# Sheet1.net
KiCad netlist of a schematic drawn in Altium Designer
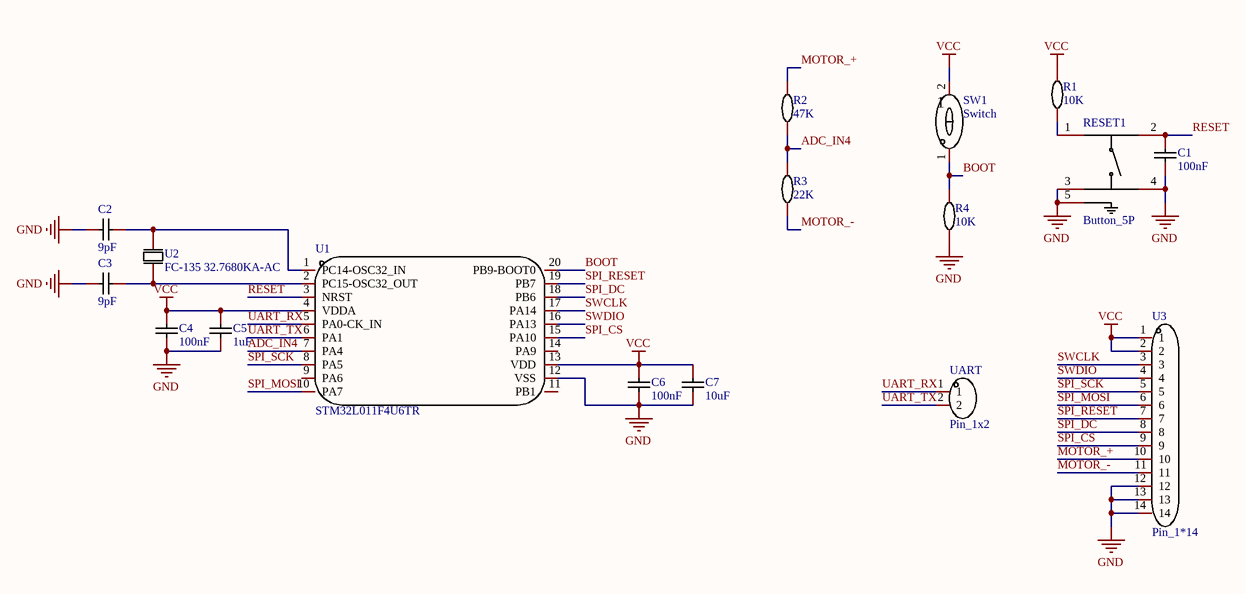
[diagram p0: Sheet1.SchDoc]

(export (version "E")
  (design (tool "Eeschema 10.0.6"))
  (components
    (comp (ref "C1") (value "100nF") (footprint "C0402") (libsource (lib "MySchlib") (part "C")))
    (comp (ref "C2") (value "9pF") (footprint "C0402") (libsource (lib "MySchlib") (part "C")))
    (comp (ref "C3") (value "9pF") (footprint "C0402") (libsource (lib "MySchlib") (part "C")))
    (comp (ref "C4") (value "100nF") (footprint "C0402") (libsource (lib "MySchlib") (part "C")))
    (comp (ref "C5") (value "1uF") (footprint "C0402") (libsource (lib "MySchlib") (part "C")))
    (comp (ref "C6") (value "100nF") (footprint "C0402") (libsource (lib "MySchlib") (part "C")))
    (comp (ref "C7") (value "10uF") (footprint "C0402") (libsource (lib "MySchlib") (part "C")))
    (comp (ref "R1") (value "10K") (footprint "R0603") (libsource (lib "MySchlib") (part "R")))
    (comp (ref "R2") (value "47K") (footprint "R0603") (libsource (lib "MySchlib") (part "R")))
    (comp (ref "R3") (value "22K") (footprint "R0603") (libsource (lib "MySchlib") (part "R")))
    (comp (ref "R4") (value "10K") (footprint "R0603") (libsource (lib "MySchlib") (part "R")))
    (comp (ref "RESET1")
      (value "Button_5P")
      (footprint "Button_3.3x3.3mm")
      (libsource (lib "MySchlib") (part "Button_5P"))
    )
    (comp (ref "SW1") (value "Switch") (footprint "Switch") (libsource (lib "MySchlib") (part "Switch")))
    (comp (ref "U1")
      (value "STM32L011F4U6TR")
      (footprint "STM32L011F4")
      (libsource (lib "MySchlib") (part "STM32L011F4"))
    )
    (comp (ref "U2")
      (value "FC-135 32.7680KA-AC")
      (footprint "CRYSTAL-SMD_L3.2-W1.5")
      (libsource (lib "MySchlib") (part "FC-135 32.7680KA-AC"))
    )
    (comp (ref "U3") (value "Pin_1*14") (footprint "Pin_1*14") (libsource (lib "MySchlib") (part "Pin_1*14")))
    (comp (ref "UART")
      (value "Pin_1x2")
      (footprint "Pin1x2_2.54mm")
      (libsource (lib "MySchlib") (part "Pin_1x2"))
    )
  )
  (nets
    (net (code "1") (name "/ADC_IN4") (class "Default")
      (node (ref "R2") (pin "1") (pinfunction "1_1") (pintype "passive"))
      (node (ref "R3") (pin "2") (pinfunction "2_2") (pintype "passive"))
      (node (ref "U1") (pin "7") (pinfunction "PA4_7") (pintype "passive"))
    )
    (net (code "2") (name "/BOOT") (class "Default")
      (node (ref "R4") (pin "2") (pinfunction "2_2") (pintype "passive"))
      (node (ref "SW1") (pin "1") (pinfunction "PIN1_1") (pintype "passive"))
      (node (ref "U1") (pin "20") (pinfunction "PB9-BOOT0_20") (pintype "passive"))
    )
    (net (code "3") (name "/MOTOR_+") (class "Default")
      (node (ref "R2") (pin "2") (pinfunction "2_2") (pintype "passive"))
      (node (ref "U3") (pin "10") (pinfunction "10_10") (pintype "passive"))
    )
    (net (code "4") (name "/MOTOR_-") (class "Default")
      (node (ref "R3") (pin "1") (pinfunction "1_1") (pintype "passive"))
      (node (ref "U3") (pin "11") (pinfunction "11_11") (pintype "passive"))
    )
    (net (code "5") (name "/RESET") (class "Default")
      (node (ref "C1") (pin "2") (pinfunction "2_2") (pintype "passive"))
      (node (ref "RESET1") (pin "2") (pinfunction "B_2") (pintype "passive"))
      (node (ref "U1") (pin "3") (pinfunction "NRST_3") (pintype "passive"))
    )
    (net (code "6") (name "/SPI_CS") (class "Default")
      (node (ref "U1") (pin "15") (pinfunction "PA10_15") (pintype "passive"))
      (node (ref "U3") (pin "9") (pinfunction "9_9") (pintype "passive"))
    )
    (net (code "7") (name "/SPI_DC") (class "Default")
      (node (ref "U1") (pin "18") (pinfunction "PB6_18") (pintype "passive"))
      (node (ref "U3") (pin "8") (pinfunction "8_8") (pintype "passive"))
    )
    (net (code "8") (name "/SPI_MOSI") (class "Default")
      (node (ref "U1") (pin "10") (pinfunction "PA7_10") (pintype "passive"))
      (node (ref "U3") (pin "6") (pinfunction "6_6") (pintype "passive"))
    )
    (net (code "9") (name "/SPI_RESET") (class "Default")
      (node (ref "U1") (pin "19") (pinfunction "PB7_19") (pintype "passive"))
      (node (ref "U3") (pin "7") (pinfunction "7_7") (pintype "passive"))
    )
    (net (code "10") (name "/SPI_SCK") (class "Default")
      (node (ref "U1") (pin "8") (pinfunction "PA5_8") (pintype "passive"))
      (node (ref "U3") (pin "5") (pinfunction "5_5") (pintype "passive"))
    )
    (net (code "11") (name "/SWCLK") (class "Default")
      (node (ref "U1") (pin "17") (pinfunction "PA14_17") (pintype "passive"))
      (node (ref "U3") (pin "3") (pinfunction "3_3") (pintype "passive"))
    )
    (net (code "12") (name "/SWDIO") (class "Default")
      (node (ref "U1") (pin "16") (pinfunction "PA13_16") (pintype "passive"))
      (node (ref "U3") (pin "4") (pinfunction "4_4") (pintype "passive"))
    )
    (net (code "13") (name "/UART_RX") (class "Default")
      (node (ref "U1") (pin "5") (pinfunction "PA0-CK_IN_5") (pintype "passive"))
      (node (ref "UART") (pin "1") (pinfunction "1_1") (pintype "passive"))
    )
    (net (code "14") (name "/UART_TX") (class "Default")
      (node (ref "U1") (pin "6") (pinfunction "PA1_6") (pintype "passive"))
      (node (ref "UART") (pin "2") (pinfunction "2_2") (pintype "passive"))
    )
    (net (code "15") (name "GND") (class "Default")
      (node (ref "C1") (pin "1") (pinfunction "1_1") (pintype "passive"))
      (node (ref "C2") (pin "1") (pinfunction "1_1") (pintype "passive"))
      (node (ref "C3") (pin "1") (pinfunction "1_1") (pintype "passive"))
      (node (ref "C4") (pin "1") (pinfunction "1_1") (pintype "passive"))
      (node (ref "C5") (pin "1") (pinfunction "1_1") (pintype "passive"))
      (node (ref "C6") (pin "1") (pinfunction "1_1") (pintype "passive"))
      (node (ref "C7") (pin "1") (pinfunction "1_1") (pintype "passive"))
      (node (ref "R4") (pin "1") (pinfunction "1_1") (pintype "passive"))
      (node (ref "RESET1") (pin "3") (pinfunction "C_3") (pintype "passive"))
      (node (ref "RESET1") (pin "4") (pinfunction "D_4") (pintype "passive"))
      (node (ref "RESET1") (pin "5") (pinfunction "GND_5") (pintype "passive"))
      (node (ref "U1") (pin "12") (pinfunction "VSS_12") (pintype "passive"))
      (node (ref "U3") (pin "12") (pinfunction "12_12") (pintype "passive"))
      (node (ref "U3") (pin "13") (pinfunction "13_13") (pintype "passive"))
      (node (ref "U3") (pin "14") (pinfunction "14_14") (pintype "passive"))
    )
    (net (code "16") (name "Net-(RESET1-A)") (class "Default")
      (node (ref "R1") (pin "1") (pinfunction "1_1") (pintype "passive"))
      (node (ref "RESET1") (pin "1") (pinfunction "A_1") (pintype "passive"))
    )
    (net (code "17") (name "Net-(U1-PC14-OSC32_IN)") (class "Default")
      (node (ref "C2") (pin "2") (pinfunction "2_2") (pintype "passive"))
      (node (ref "U1") (pin "1") (pinfunction "PC14-OSC32_IN_1") (pintype "passive"))
      (node (ref "U2") (pin "2") (pinfunction "OSC2_2") (pintype "passive"))
    )
    (net (code "18") (name "Net-(U1-PC15-OSC32_OUT)") (class "Default")
      (node (ref "C3") (pin "2") (pinfunction "2_2") (pintype "passive"))
      (node (ref "U1") (pin "2") (pinfunction "PC15-OSC32_OUT_2") (pintype "passive"))
      (node (ref "U2") (pin "1") (pinfunction "OSC1_1") (pintype "passive"))
    )
    (net (code "19") (name "VCC") (class "Default")
      (node (ref "C4") (pin "2") (pinfunction "2_2") (pintype "passive"))
      (node (ref "C5") (pin "2") (pinfunction "2_2") (pintype "passive"))
      (node (ref "C6") (pin "2") (pinfunction "2_2") (pintype "passive"))
      (node (ref "C7") (pin "2") (pinfunction "2_2") (pintype "passive"))
      (node (ref "R1") (pin "2") (pinfunction "2_2") (pintype "passive"))
      (node (ref "SW1") (pin "2") (pinfunction "PIN2_2") (pintype "passive"))
      (node (ref "U1") (pin "13") (pinfunction "VDD_13") (pintype "passive"))
      (node (ref "U1") (pin "4") (pinfunction "VDDA_4") (pintype "passive"))
      (node (ref "U3") (pin "1") (pinfunction "1_1") (pintype "passive"))
      (node (ref "U3") (pin "2") (pinfunction "2_2") (pintype "passive"))
    )
    (net (code "20") (name "unconnected-(U1-PA6-Pad9)") (class "Default")
      (node (ref "U1") (pin "9") (pinfunction "PA6_9") (pintype "passive"))
    )
    (net (code "21") (name "unconnected-(U1-PA9-Pad14)") (class "Default")
      (node (ref "U1") (pin "14") (pinfunction "PA9_14") (pintype "passive"))
    )
    (net (code "22") (name "unconnected-(U1-PB1-Pad11)") (class "Default")
      (node (ref "U1") (pin "11") (pinfunction "PB1_11") (pintype "passive"))
    )
  )
)
